# S181A.net
KiCad netlist of a schematic drawn in EAGLE
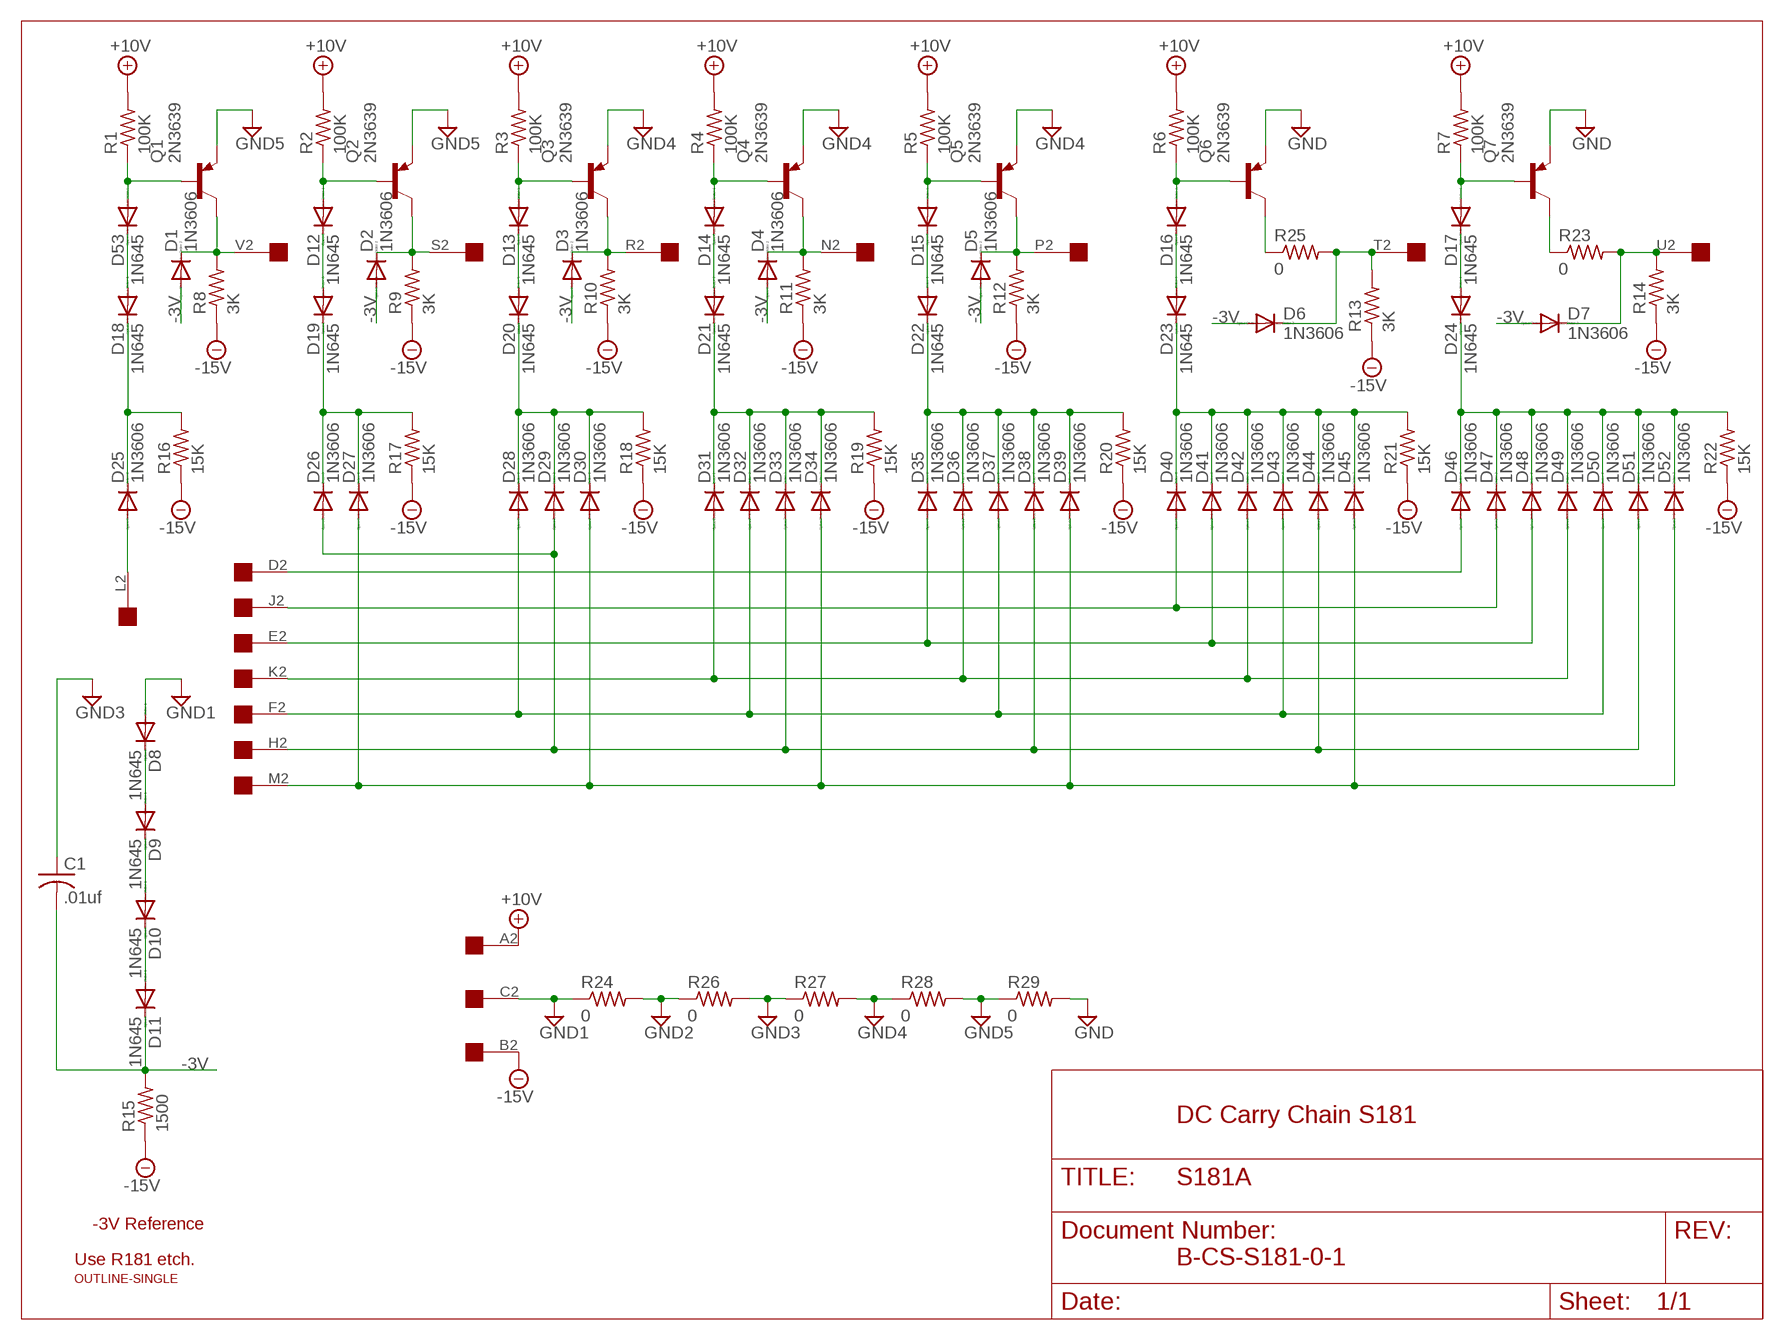
[diagram p0: schematic, sheet 1]

(export (version "E")
  (design (tool "Eeschema 10.0.6"))
  (components
    (comp (ref "C1")
      (value ".01uf")
      (footprint "eagle-import:C050-025X075")
      (libsource (lib "eagle-import") (part "C-US050-025X075"))
    )
    (comp (ref "D1")
      (value "1N3606")
      (footprint "eagle-import:DO35-10")
      (libsource (lib "eagle-import") (part "1N4148DO35-10"))
    )
    (comp (ref "D2")
      (value "1N3606")
      (footprint "eagle-import:DO35-10")
      (libsource (lib "eagle-import") (part "1N4148DO35-10"))
    )
    (comp (ref "D3")
      (value "1N3606")
      (footprint "eagle-import:DO35-10")
      (libsource (lib "eagle-import") (part "1N4148DO35-10"))
    )
    (comp (ref "D4")
      (value "1N3606")
      (footprint "eagle-import:DO35-10")
      (libsource (lib "eagle-import") (part "1N4148DO35-10"))
    )
    (comp (ref "D5")
      (value "1N3606")
      (footprint "eagle-import:DO35-10")
      (libsource (lib "eagle-import") (part "1N4148DO35-10"))
    )
    (comp (ref "D6")
      (value "1N3606")
      (footprint "eagle-import:DO35-10")
      (libsource (lib "eagle-import") (part "1N4148DO35-10"))
    )
    (comp (ref "D7")
      (value "1N3606")
      (footprint "eagle-import:DO35-10")
      (libsource (lib "eagle-import") (part "1N4148DO35-10"))
    )
    (comp (ref "D8")
      (value "1N645")
      (footprint "eagle-import:DO35-10")
      (libsource (lib "eagle-import") (part "1N4148DO35-10"))
    )
    (comp (ref "D9")
      (value "1N645")
      (footprint "eagle-import:DO35-10")
      (libsource (lib "eagle-import") (part "1N4148DO35-10"))
    )
    (comp (ref "D10")
      (value "1N645")
      (footprint "eagle-import:DO35-10")
      (libsource (lib "eagle-import") (part "1N4148DO35-10"))
    )
    (comp (ref "D11")
      (value "1N645")
      (footprint "eagle-import:DO35-10")
      (libsource (lib "eagle-import") (part "1N4148DO35-10"))
    )
    (comp (ref "D12")
      (value "1N645")
      (footprint "eagle-import:DO35-10")
      (libsource (lib "eagle-import") (part "1N4148DO35-10"))
    )
    (comp (ref "D13")
      (value "1N645")
      (footprint "eagle-import:DO35-10")
      (libsource (lib "eagle-import") (part "1N4148DO35-10"))
    )
    (comp (ref "D14")
      (value "1N645")
      (footprint "eagle-import:DO35-10")
      (libsource (lib "eagle-import") (part "1N4148DO35-10"))
    )
    (comp (ref "D15")
      (value "1N645")
      (footprint "eagle-import:DO35-10")
      (libsource (lib "eagle-import") (part "1N4148DO35-10"))
    )
    (comp (ref "D16")
      (value "1N645")
      (footprint "eagle-import:DO35-10")
      (libsource (lib "eagle-import") (part "1N4148DO35-10"))
    )
    (comp (ref "D17")
      (value "1N645")
      (footprint "eagle-import:DO35-10")
      (libsource (lib "eagle-import") (part "1N4148DO35-10"))
    )
    (comp (ref "D18")
      (value "1N645")
      (footprint "eagle-import:DO35-10")
      (libsource (lib "eagle-import") (part "1N4148DO35-10"))
    )
    (comp (ref "D19")
      (value "1N645")
      (footprint "eagle-import:DO35-10")
      (libsource (lib "eagle-import") (part "1N4148DO35-10"))
    )
    (comp (ref "D20")
      (value "1N645")
      (footprint "eagle-import:DO35-10")
      (libsource (lib "eagle-import") (part "1N4148DO35-10"))
    )
    (comp (ref "D21")
      (value "1N645")
      (footprint "eagle-import:DO35-10")
      (libsource (lib "eagle-import") (part "1N4148DO35-10"))
    )
    (comp (ref "D22")
      (value "1N645")
      (footprint "eagle-import:DO35-10")
      (libsource (lib "eagle-import") (part "1N4148DO35-10"))
    )
    (comp (ref "D23")
      (value "1N645")
      (footprint "eagle-import:DO35-10")
      (libsource (lib "eagle-import") (part "1N4148DO35-10"))
    )
    (comp (ref "D24")
      (value "1N645")
      (footprint "eagle-import:DO35-10")
      (libsource (lib "eagle-import") (part "1N4148DO35-10"))
    )
    (comp (ref "D25")
      (value "1N3606")
      (footprint "eagle-import:DO35-10")
      (libsource (lib "eagle-import") (part "1N4148DO35-10"))
    )
    (comp (ref "D26")
      (value "1N3606")
      (footprint "eagle-import:DO35-10")
      (libsource (lib "eagle-import") (part "1N4148DO35-10"))
    )
    (comp (ref "D27")
      (value "1N3606")
      (footprint "eagle-import:DO35-10")
      (libsource (lib "eagle-import") (part "1N4148DO35-10"))
    )
    (comp (ref "D28")
      (value "1N3606")
      (footprint "eagle-import:DO35-10")
      (libsource (lib "eagle-import") (part "1N4148DO35-10"))
    )
    (comp (ref "D29")
      (value "1N3606")
      (footprint "eagle-import:DO35-10")
      (libsource (lib "eagle-import") (part "1N4148DO35-10"))
    )
    (comp (ref "D30")
      (value "1N3606")
      (footprint "eagle-import:DO35-10")
      (libsource (lib "eagle-import") (part "1N4148DO35-10"))
    )
    (comp (ref "D31")
      (value "1N3606")
      (footprint "eagle-import:DO35-10")
      (libsource (lib "eagle-import") (part "1N4148DO35-10"))
    )
    (comp (ref "D32")
      (value "1N3606")
      (footprint "eagle-import:DO35-10")
      (libsource (lib "eagle-import") (part "1N4148DO35-10"))
    )
    (comp (ref "D33")
      (value "1N3606")
      (footprint "eagle-import:DO35-10")
      (libsource (lib "eagle-import") (part "1N4148DO35-10"))
    )
    (comp (ref "D34")
      (value "1N3606")
      (footprint "eagle-import:DO35-10")
      (libsource (lib "eagle-import") (part "1N4148DO35-10"))
    )
    (comp (ref "D35")
      (value "1N3606")
      (footprint "eagle-import:DO35-10")
      (libsource (lib "eagle-import") (part "1N4148DO35-10"))
    )
    (comp (ref "D36")
      (value "1N3606")
      (footprint "eagle-import:DO35-10")
      (libsource (lib "eagle-import") (part "1N4148DO35-10"))
    )
    (comp (ref "D37")
      (value "1N3606")
      (footprint "eagle-import:DO35-10")
      (libsource (lib "eagle-import") (part "1N4148DO35-10"))
    )
    (comp (ref "D38")
      (value "1N3606")
      (footprint "eagle-import:DO35-10")
      (libsource (lib "eagle-import") (part "1N4148DO35-10"))
    )
    (comp (ref "D39")
      (value "1N3606")
      (footprint "eagle-import:DO35-10")
      (libsource (lib "eagle-import") (part "1N4148DO35-10"))
    )
    (comp (ref "D40")
      (value "1N3606")
      (footprint "eagle-import:DO35-10")
      (libsource (lib "eagle-import") (part "1N4148DO35-10"))
    )
    (comp (ref "D41")
      (value "1N3606")
      (footprint "eagle-import:DO35-10")
      (libsource (lib "eagle-import") (part "1N4148DO35-10"))
    )
    (comp (ref "D42")
      (value "1N3606")
      (footprint "eagle-import:DO35-10")
      (libsource (lib "eagle-import") (part "1N4148DO35-10"))
    )
    (comp (ref "D43")
      (value "1N3606")
      (footprint "eagle-import:DO35-10")
      (libsource (lib "eagle-import") (part "1N4148DO35-10"))
    )
    (comp (ref "D44")
      (value "1N3606")
      (footprint "eagle-import:DO35-10")
      (libsource (lib "eagle-import") (part "1N4148DO35-10"))
    )
    (comp (ref "D45")
      (value "1N3606")
      (footprint "eagle-import:DO35-10")
      (libsource (lib "eagle-import") (part "1N4148DO35-10"))
    )
    (comp (ref "D46")
      (value "1N3606")
      (footprint "eagle-import:DO35-10")
      (libsource (lib "eagle-import") (part "1N4148DO35-10"))
    )
    (comp (ref "D47")
      (value "1N3606")
      (footprint "eagle-import:DO35-10")
      (libsource (lib "eagle-import") (part "1N4148DO35-10"))
    )
    (comp (ref "D48")
      (value "1N3606")
      (footprint "eagle-import:DO35-10")
      (libsource (lib "eagle-import") (part "1N4148DO35-10"))
    )
    (comp (ref "D49")
      (value "1N3606")
      (footprint "eagle-import:DO35-10")
      (libsource (lib "eagle-import") (part "1N4148DO35-10"))
    )
    (comp (ref "D50")
      (value "1N3606")
      (footprint "eagle-import:DO35-10")
      (libsource (lib "eagle-import") (part "1N4148DO35-10"))
    )
    (comp (ref "D51")
      (value "1N3606")
      (footprint "eagle-import:DO35-10")
      (libsource (lib "eagle-import") (part "1N4148DO35-10"))
    )
    (comp (ref "D52")
      (value "1N3606")
      (footprint "eagle-import:DO35-10")
      (libsource (lib "eagle-import") (part "1N4148DO35-10"))
    )
    (comp (ref "D53")
      (value "1N645")
      (footprint "eagle-import:DO35-10")
      (libsource (lib "eagle-import") (part "1N4148DO35-10"))
    )
    (comp (ref "Q1")
      (value "2N3639")
      (footprint "eagle-import:TO39")
      (libsource (lib "eagle-import") (part "2N3637"))
    )
    (comp (ref "Q2")
      (value "2N3639")
      (footprint "eagle-import:TO39")
      (libsource (lib "eagle-import") (part "2N3637"))
    )
    (comp (ref "Q3")
      (value "2N3639")
      (footprint "eagle-import:TO39")
      (libsource (lib "eagle-import") (part "2N3637"))
    )
    (comp (ref "Q4")
      (value "2N3639")
      (footprint "eagle-import:TO39")
      (libsource (lib "eagle-import") (part "2N3637"))
    )
    (comp (ref "Q5")
      (value "2N3639")
      (footprint "eagle-import:TO39")
      (libsource (lib "eagle-import") (part "2N3637"))
    )
    (comp (ref "Q6")
      (value "2N3639")
      (footprint "eagle-import:TO39")
      (libsource (lib "eagle-import") (part "2N3637"))
    )
    (comp (ref "Q7")
      (value "2N3639")
      (footprint "eagle-import:TO39")
      (libsource (lib "eagle-import") (part "2N3637"))
    )
    (comp (ref "R1")
      (value "100K")
      (footprint "eagle-import:0207_10")
      (libsource (lib "eagle-import") (part "R-US_0207/10"))
    )
    (comp (ref "R2")
      (value "100K")
      (footprint "eagle-import:0207_10")
      (libsource (lib "eagle-import") (part "R-US_0207/10"))
    )
    (comp (ref "R3")
      (value "100K")
      (footprint "eagle-import:0207_10")
      (libsource (lib "eagle-import") (part "R-US_0207/10"))
    )
    (comp (ref "R4")
      (value "100K")
      (footprint "eagle-import:0207_10")
      (libsource (lib "eagle-import") (part "R-US_0207/10"))
    )
    (comp (ref "R5")
      (value "100K")
      (footprint "eagle-import:0207_10")
      (libsource (lib "eagle-import") (part "R-US_0207/10"))
    )
    (comp (ref "R6")
      (value "100K")
      (footprint "eagle-import:0207_10")
      (libsource (lib "eagle-import") (part "R-US_0207/10"))
    )
    (comp (ref "R7")
      (value "100K")
      (footprint "eagle-import:0207_10")
      (libsource (lib "eagle-import") (part "R-US_0207/10"))
    )
    (comp (ref "R8")
      (value "3K")
      (footprint "eagle-import:0207_10")
      (libsource (lib "eagle-import") (part "R-US_0207/10"))
    )
    (comp (ref "R9")
      (value "3K")
      (footprint "eagle-import:0207_10")
      (libsource (lib "eagle-import") (part "R-US_0207/10"))
    )
    (comp (ref "R10")
      (value "3K")
      (footprint "eagle-import:0207_10")
      (libsource (lib "eagle-import") (part "R-US_0207/10"))
    )
    (comp (ref "R11")
      (value "3K")
      (footprint "eagle-import:0207_10")
      (libsource (lib "eagle-import") (part "R-US_0207/10"))
    )
    (comp (ref "R12")
      (value "3K")
      (footprint "eagle-import:0207_10")
      (libsource (lib "eagle-import") (part "R-US_0207/10"))
    )
    (comp (ref "R13")
      (value "3K")
      (footprint "eagle-import:0207_10")
      (libsource (lib "eagle-import") (part "R-US_0207/10"))
    )
    (comp (ref "R14")
      (value "3K")
      (footprint "eagle-import:0207_10")
      (libsource (lib "eagle-import") (part "R-US_0207/10"))
    )
    (comp (ref "R15")
      (value "1500")
      (footprint "eagle-import:0207_10")
      (libsource (lib "eagle-import") (part "R-US_0207/10"))
    )
    (comp (ref "R16")
      (value "15K")
      (footprint "eagle-import:0207_10")
      (libsource (lib "eagle-import") (part "R-US_0207/10"))
    )
    (comp (ref "R17")
      (value "15K")
      (footprint "eagle-import:0207_10")
      (libsource (lib "eagle-import") (part "R-US_0207/10"))
    )
    (comp (ref "R18")
      (value "15K")
      (footprint "eagle-import:0207_10")
      (libsource (lib "eagle-import") (part "R-US_0207/10"))
    )
    (comp (ref "R19")
      (value "15K")
      (footprint "eagle-import:0207_10")
      (libsource (lib "eagle-import") (part "R-US_0207/10"))
    )
    (comp (ref "R20")
      (value "15K")
      (footprint "eagle-import:0207_10")
      (libsource (lib "eagle-import") (part "R-US_0207/10"))
    )
    (comp (ref "R21")
      (value "15K")
      (footprint "eagle-import:0207_10")
      (libsource (lib "eagle-import") (part "R-US_0207/10"))
    )
    (comp (ref "R22")
      (value "15K")
      (footprint "eagle-import:0207_10")
      (libsource (lib "eagle-import") (part "R-US_0207/10"))
    )
    (comp (ref "R23")
      (value "0")
      (footprint "eagle-import:0207_10")
      (libsource (lib "eagle-import") (part "R-US_0207/10"))
    )
    (comp (ref "R24")
      (value "0")
      (footprint "eagle-import:0207_10")
      (libsource (lib "eagle-import") (part "R-US_0207/10"))
    )
    (comp (ref "R25")
      (value "0")
      (footprint "eagle-import:0207_10")
      (libsource (lib "eagle-import") (part "R-US_0207/10"))
    )
    (comp (ref "R26")
      (value "0")
      (footprint "eagle-import:0207_10")
      (libsource (lib "eagle-import") (part "R-US_0207/10"))
    )
    (comp (ref "R27")
      (value "0")
      (footprint "eagle-import:0207_10")
      (libsource (lib "eagle-import") (part "R-US_0207/10"))
    )
    (comp (ref "R28")
      (value "0")
      (footprint "eagle-import:0207_10")
      (libsource (lib "eagle-import") (part "R-US_0207/10"))
    )
    (comp (ref "R29")
      (value "0")
      (footprint "eagle-import:0207_10")
      (libsource (lib "eagle-import") (part "R-US_0207/10"))
    )
    (comp (ref "U$1")
      (value "OUTLINE-SINGLE")
      (footprint "eagle-import:SINGLE")
      (libsource (lib "eagle-import") (part "OUTLINE-SINGLE"))
    )
    (comp (ref "U$2")
      (value "EDGE-1")
      (footprint "eagle-import:EDGE-CON1")
      (libsource (lib "eagle-import") (part "EDGE-1"))
    )
  )
  (nets
    (net (code "1") (name "+10V") (class "Default")
      (node (ref "R1") (pin "2") (pinfunction "2_2") (pintype "passive"))
      (node (ref "R2") (pin "2") (pinfunction "2_2") (pintype "passive"))
      (node (ref "R3") (pin "2") (pinfunction "2_2") (pintype "passive"))
      (node (ref "R4") (pin "2") (pinfunction "2_2") (pintype "passive"))
      (node (ref "R5") (pin "2") (pinfunction "2_2") (pintype "passive"))
      (node (ref "R6") (pin "2") (pinfunction "2_2") (pintype "passive"))
      (node (ref "R7") (pin "2") (pinfunction "2_2") (pintype "passive"))
      (node (ref "U$2") (pin "A2") (pinfunction "1_A2") (pintype "bidirectional"))
    )
    (net (code "2") (name "-15V") (class "Default")
      (node (ref "R10") (pin "1") (pinfunction "1_1") (pintype "passive"))
      (node (ref "R11") (pin "1") (pinfunction "1_1") (pintype "passive"))
      (node (ref "R12") (pin "1") (pinfunction "1_1") (pintype "passive"))
      (node (ref "R13") (pin "1") (pinfunction "1_1") (pintype "passive"))
      (node (ref "R14") (pin "1") (pinfunction "1_1") (pintype "passive"))
      (node (ref "R15") (pin "1") (pinfunction "1_1") (pintype "passive"))
      (node (ref "R16") (pin "1") (pinfunction "1_1") (pintype "passive"))
      (node (ref "R17") (pin "1") (pinfunction "1_1") (pintype "passive"))
      (node (ref "R18") (pin "1") (pinfunction "1_1") (pintype "passive"))
      (node (ref "R19") (pin "1") (pinfunction "1_1") (pintype "passive"))
      (node (ref "R20") (pin "1") (pinfunction "1_1") (pintype "passive"))
      (node (ref "R21") (pin "1") (pinfunction "1_1") (pintype "passive"))
      (node (ref "R22") (pin "1") (pinfunction "1_1") (pintype "passive"))
      (node (ref "R8") (pin "1") (pinfunction "1_1") (pintype "passive"))
      (node (ref "R9") (pin "1") (pinfunction "1_1") (pintype "passive"))
      (node (ref "U$2") (pin "B2") (pinfunction "1_B2") (pintype "bidirectional"))
    )
    (net (code "3") (name "/-3V") (class "Default")
      (node (ref "C1") (pin "2") (pinfunction "2_2") (pintype "passive"))
      (node (ref "D1") (pin "A") (pinfunction "A_A") (pintype "passive"))
      (node (ref "D11") (pin "C") (pinfunction "C_C") (pintype "passive"))
      (node (ref "D2") (pin "A") (pinfunction "A_A") (pintype "passive"))
      (node (ref "D3") (pin "A") (pinfunction "A_A") (pintype "passive"))
      (node (ref "D4") (pin "A") (pinfunction "A_A") (pintype "passive"))
      (node (ref "D5") (pin "A") (pinfunction "A_A") (pintype "passive"))
      (node (ref "D6") (pin "A") (pinfunction "A_A") (pintype "passive"))
      (node (ref "D7") (pin "A") (pinfunction "A_A") (pintype "passive"))
      (node (ref "R15") (pin "2") (pinfunction "2_2") (pintype "passive"))
    )
    (net (code "4") (name "GND") (class "Default")
      (node (ref "Q6") (pin "1") (pinfunction "E_1") (pintype "passive"))
      (node (ref "Q7") (pin "1") (pinfunction "E_1") (pintype "passive"))
      (node (ref "R29") (pin "2") (pinfunction "2_2") (pintype "passive"))
    )
    (net (code "5") (name "GND1") (class "Default")
      (node (ref "D8") (pin "A") (pinfunction "A_A") (pintype "passive"))
      (node (ref "R24") (pin "1") (pinfunction "1_1") (pintype "passive"))
      (node (ref "U$2") (pin "C2") (pinfunction "1_C2") (pintype "bidirectional"))
    )
    (net (code "6") (name "GND2") (class "Default")
      (node (ref "R24") (pin "2") (pinfunction "2_2") (pintype "passive"))
      (node (ref "R26") (pin "1") (pinfunction "1_1") (pintype "passive"))
    )
    (net (code "7") (name "GND3") (class "Default")
      (node (ref "C1") (pin "1") (pinfunction "1_1") (pintype "passive"))
      (node (ref "R26") (pin "2") (pinfunction "2_2") (pintype "passive"))
      (node (ref "R27") (pin "1") (pinfunction "1_1") (pintype "passive"))
    )
    (net (code "8") (name "GND4") (class "Default")
      (node (ref "Q3") (pin "1") (pinfunction "E_1") (pintype "passive"))
      (node (ref "Q4") (pin "1") (pinfunction "E_1") (pintype "passive"))
      (node (ref "Q5") (pin "1") (pinfunction "E_1") (pintype "passive"))
      (node (ref "R27") (pin "2") (pinfunction "2_2") (pintype "passive"))
      (node (ref "R28") (pin "1") (pinfunction "1_1") (pintype "passive"))
    )
    (net (code "9") (name "GND5") (class "Default")
      (node (ref "Q1") (pin "1") (pinfunction "E_1") (pintype "passive"))
      (node (ref "Q2") (pin "1") (pinfunction "E_1") (pintype "passive"))
      (node (ref "R28") (pin "2") (pinfunction "2_2") (pintype "passive"))
      (node (ref "R29") (pin "1") (pinfunction "1_1") (pintype "passive"))
    )
    (net (code "10") (name "Net-(D8-PadC)") (class "Default")
      (node (ref "D8") (pin "C") (pinfunction "C_C") (pintype "passive"))
      (node (ref "D9") (pin "A") (pinfunction "A_A") (pintype "passive"))
    )
    (net (code "11") (name "Net-(D10-PadA)") (class "Default")
      (node (ref "D10") (pin "A") (pinfunction "A_A") (pintype "passive"))
      (node (ref "D9") (pin "C") (pinfunction "C_C") (pintype "passive"))
    )
    (net (code "12") (name "Net-(D10-PadC)") (class "Default")
      (node (ref "D10") (pin "C") (pinfunction "C_C") (pintype "passive"))
      (node (ref "D11") (pin "A") (pinfunction "A_A") (pintype "passive"))
    )
    (net (code "13") (name "Net-(D12-PadC)") (class "Default")
      (node (ref "D12") (pin "C") (pinfunction "C_C") (pintype "passive"))
      (node (ref "D19") (pin "A") (pinfunction "A_A") (pintype "passive"))
    )
    (net (code "14") (name "Net-(D13-PadC)") (class "Default")
      (node (ref "D13") (pin "C") (pinfunction "C_C") (pintype "passive"))
      (node (ref "D20") (pin "A") (pinfunction "A_A") (pintype "passive"))
    )
    (net (code "15") (name "Net-(D14-PadC)") (class "Default")
      (node (ref "D14") (pin "C") (pinfunction "C_C") (pintype "passive"))
      (node (ref "D21") (pin "A") (pinfunction "A_A") (pintype "passive"))
    )
    (net (code "16") (name "Net-(D15-PadC)") (class "Default")
      (node (ref "D15") (pin "C") (pinfunction "C_C") (pintype "passive"))
      (node (ref "D22") (pin "A") (pinfunction "A_A") (pintype "passive"))
    )
    (net (code "17") (name "Net-(D16-PadC)") (class "Default")
      (node (ref "D16") (pin "C") (pinfunction "C_C") (pintype "passive"))
      (node (ref "D23") (pin "A") (pinfunction "A_A") (pintype "passive"))
    )
    (net (code "18") (name "Net-(D17-PadC)") (class "Default")
      (node (ref "D17") (pin "C") (pinfunction "C_C") (pintype "passive"))
      (node (ref "D24") (pin "A") (pinfunction "A_A") (pintype "passive"))
    )
    (net (code "19") (name "Net-(D18-PadA)") (class "Default")
      (node (ref "D18") (pin "A") (pinfunction "A_A") (pintype "passive"))
      (node (ref "D53") (pin "C") (pinfunction "C_C") (pintype "passive"))
    )
    (net (code "20") (name "Net-(D18-PadC)") (class "Default")
      (node (ref "D18") (pin "C") (pinfunction "C_C") (pintype "passive"))
      (node (ref "D25") (pin "C") (pinfunction "C_C") (pintype "passive"))
      (node (ref "R16") (pin "2") (pinfunction "2_2") (pintype "passive"))
    )
    (net (code "21") (name "Net-(D19-PadC)") (class "Default")
      (node (ref "D19") (pin "C") (pinfunction "C_C") (pintype "passive"))
      (node (ref "D26") (pin "C") (pinfunction "C_C") (pintype "passive"))
      (node (ref "D27") (pin "C") (pinfunction "C_C") (pintype "passive"))
      (node (ref "R17") (pin "2") (pinfunction "2_2") (pintype "passive"))
    )
    (net (code "22") (name "Net-(D20-PadC)") (class "Default")
      (node (ref "D20") (pin "C") (pinfunction "C_C") (pintype "passive"))
      (node (ref "D28") (pin "C") (pinfunction "C_C") (pintype "passive"))
      (node (ref "D29") (pin "C") (pinfunction "C_C") (pintype "passive"))
      (node (ref "D30") (pin "C") (pinfunction "C_C") (pintype "passive"))
      (node (ref "R18") (pin "2") (pinfunction "2_2") (pintype "passive"))
    )
    (net (code "23") (name "Net-(D21-PadC)") (class "Default")
      (node (ref "D21") (pin "C") (pinfunction "C_C") (pintype "passive"))
      (node (ref "D31") (pin "C") (pinfunction "C_C") (pintype "passive"))
      (node (ref "D32") (pin "C") (pinfunction "C_C") (pintype "passive"))
      (node (ref "D33") (pin "C") (pinfunction "C_C") (pintype "passive"))
      (node (ref "D34") (pin "C") (pinfunction "C_C") (pintype "passive"))
      (node (ref "R19") (pin "2") (pinfunction "2_2") (pintype "passive"))
    )
    (net (code "24") (name "Net-(D22-PadC)") (class "Default")
      (node (ref "D22") (pin "C") (pinfunction "C_C") (pintype "passive"))
      (node (ref "D35") (pin "C") (pinfunction "C_C") (pintype "passive"))
      (node (ref "D36") (pin "C") (pinfunction "C_C") (pintype "passive"))
      (node (ref "D37") (pin "C") (pinfunction "C_C") (pintype "passive"))
      (node (ref "D38") (pin "C") (pinfunction "C_C") (pintype "passive"))
      (node (ref "D39") (pin "C") (pinfunction "C_C") (pintype "passive"))
      (node (ref "R20") (pin "2") (pinfunction "2_2") (pintype "passive"))
    )
    (net (code "25") (name "Net-(D23-PadC)") (class "Default")
      (node (ref "D23") (pin "C") (pinfunction "C_C") (pintype "passive"))
      (node (ref "D40") (pin "C") (pinfunction "C_C") (pintype "passive"))
      (node (ref "D41") (pin "C") (pinfunction "C_C") (pintype "passive"))
      (node (ref "D42") (pin "C") (pinfunction "C_C") (pintype "passive"))
      (node (ref "D43") (pin "C") (pinfunction "C_C") (pintype "passive"))
      (node (ref "D44") (pin "C") (pinfunction "C_C") (pintype "passive"))
      (node (ref "D45") (pin "C") (pinfunction "C_C") (pintype "passive"))
      (node (ref "R21") (pin "2") (pinfunction "2_2") (pintype "passive"))
    )
    (net (code "26") (name "Net-(D24-PadC)") (class "Default")
      (node (ref "D24") (pin "C") (pinfunction "C_C") (pintype "passive"))
      (node (ref "D46") (pin "C") (pinfunction "C_C") (pintype "passive"))
      (node (ref "D47") (pin "C") (pinfunction "C_C") (pintype "passive"))
      (node (ref "D48") (pin "C") (pinfunction "C_C") (pintype "passive"))
      (node (ref "D49") (pin "C") (pinfunction "C_C") (pintype "passive"))
      (node (ref "D50") (pin "C") (pinfunction "C_C") (pintype "passive"))
      (node (ref "D51") (pin "C") (pinfunction "C_C") (pintype "passive"))
      (node (ref "D52") (pin "C") (pinfunction "C_C") (pintype "passive"))
      (node (ref "R22") (pin "2") (pinfunction "2_2") (pintype "passive"))
    )
    (net (code "27") (name "Net-(Q1-B)") (class "Default")
      (node (ref "D53") (pin "A") (pinfunction "A_A") (pintype "passive"))
      (node (ref "Q1") (pin "2") (pinfunction "B_2") (pintype "passive"))
      (node (ref "R1") (pin "1") (pinfunction "1_1") (pintype "passive"))
    )
    (net (code "28") (name "Net-(Q1-C)") (class "Default")
      (node (ref "D1") (pin "C") (pinfunction "C_C") (pintype "passive"))
      (node (ref "Q1") (pin "3") (pinfunction "C_3") (pintype "passive"))
      (node (ref "R8") (pin "2") (pinfunction "2_2") (pintype "passive"))
      (node (ref "U$2") (pin "V2") (pinfunction "1_V2") (pintype "bidirectional"))
    )
    (net (code "29") (name "Net-(Q2-B)") (class "Default")
      (node (ref "D12") (pin "A") (pinfunction "A_A") (pintype "passive"))
      (node (ref "Q2") (pin "2") (pinfunction "B_2") (pintype "passive"))
      (node (ref "R2") (pin "1") (pinfunction "1_1") (pintype "passive"))
    )
    (net (code "30") (name "Net-(Q2-C)") (class "Default")
      (node (ref "D2") (pin "C") (pinfunction "C_C") (pintype "passive"))
      (node (ref "Q2") (pin "3") (pinfunction "C_3") (pintype "passive"))
      (node (ref "R9") (pin "2") (pinfunction "2_2") (pintype "passive"))
      (node (ref "U$2") (pin "S2") (pinfunction "1_S2") (pintype "bidirectional"))
    )
    (net (code "31") (name "Net-(Q3-B)") (class "Default")
      (node (ref "D13") (pin "A") (pinfunction "A_A") (pintype "passive"))
      (node (ref "Q3") (pin "2") (pinfunction "B_2") (pintype "passive"))
      (node (ref "R3") (pin "1") (pinfunction "1_1") (pintype "passive"))
    )
    (net (code "32") (name "Net-(Q3-C)") (class "Default")
      (node (ref "D3") (pin "C") (pinfunction "C_C") (pintype "passive"))
      (node (ref "Q3") (pin "3") (pinfunction "C_3") (pintype "passive"))
      (node (ref "R10") (pin "2") (pinfunction "2_2") (pintype "passive"))
      (node (ref "U$2") (pin "R2") (pinfunction "1_R2") (pintype "bidirectional"))
    )
    (net (code "33") (name "Net-(Q4-B)") (class "Default")
      (node (ref "D14") (pin "A") (pinfunction "A_A") (pintype "passive"))
      (node (ref "Q4") (pin "2") (pinfunction "B_2") (pintype "passive"))
      (node (ref "R4") (pin "1") (pinfunction "1_1") (pintype "passive"))
    )
    (net (code "34") (name "Net-(Q4-C)") (class "Default")
      (node (ref "D4") (pin "C") (pinfunction "C_C") (pintype "passive"))
      (node (ref "Q4") (pin "3") (pinfunction "C_3") (pintype "passive"))
      (node (ref "R11") (pin "2") (pinfunction "2_2") (pintype "passive"))
      (node (ref "U$2") (pin "N2") (pinfunction "1_N2") (pintype "bidirectional"))
    )
    (net (code "35") (name "Net-(Q5-B)") (class "Default")
      (node (ref "D15") (pin "A") (pinfunction "A_A") (pintype "passive"))
      (node (ref "Q5") (pin "2") (pinfunction "B_2") (pintype "passive"))
      (node (ref "R5") (pin "1") (pinfunction "1_1") (pintype "passive"))
    )
    (net (code "36") (name "Net-(Q5-C)") (class "Default")
      (node (ref "D5") (pin "C") (pinfunction "C_C") (pintype "passive"))
      (node (ref "Q5") (pin "3") (pinfunction "C_3") (pintype "passive"))
      (node (ref "R12") (pin "2") (pinfunction "2_2") (pintype "passive"))
      (node (ref "U$2") (pin "P2") (pinfunction "1_P2") (pintype "bidirectional"))
    )
    (net (code "37") (name "Net-(Q6-B)") (class "Default")
      (node (ref "D16") (pin "A") (pinfunction "A_A") (pintype "passive"))
      (node (ref "Q6") (pin "2") (pinfunction "B_2") (pintype "passive"))
      (node (ref "R6") (pin "1") (pinfunction "1_1") (pintype "passive"))
    )
    (net (code "38") (name "Net-(Q6-C)") (class "Default")
      (node (ref "Q6") (pin "3") (pinfunction "C_3") (pintype "passive"))
      (node (ref "R25") (pin "1") (pinfunction "1_1") (pintype "passive"))
    )
    (net (code "39") (name "Net-(Q7-B)") (class "Default")
      (node (ref "D17") (pin "A") (pinfunction "A_A") (pintype "passive"))
      (node (ref "Q7") (pin "2") (pinfunction "B_2") (pintype "passive"))
      (node (ref "R7") (pin "1") (pinfunction "1_1") (pintype "passive"))
    )
    (net (code "40") (name "Net-(Q7-C)") (class "Default")
      (node (ref "Q7") (pin "3") (pinfunction "C_3") (pintype "passive"))
      (node (ref "R23") (pin "1") (pinfunction "1_1") (pintype "passive"))
    )
    (net (code "41") (name "Net-(U$2D-1)") (class "Default")
      (node (ref "D46") (pin "A") (pinfunction "A_A") (pintype "passive"))
      (node (ref "U$2") (pin "D2") (pinfunction "1_D2") (pintype "bidirectional"))
    )
    (net (code "42") (name "Net-(U$2E-1)") (class "Default")
      (node (ref "D35") (pin "A") (pinfunction "A_A") (pintype "passive"))
      (node (ref "D41") (pin "A") (pinfunction "A_A") (pintype "passive"))
      (node (ref "D48") (pin "A") (pinfunction "A_A") (pintype "passive"))
      (node (ref "U$2") (pin "E2") (pinfunction "1_E2") (pintype "bidirectional"))
    )
    (net (code "43") (name "Net-(U$2F-1)") (class "Default")
      (node (ref "D28") (pin "A") (pinfunction "A_A") (pintype "passive"))
      (node (ref "D32") (pin "A") (pinfunction "A_A") (pintype "passive"))
      (node (ref "D37") (pin "A") (pinfunction "A_A") (pintype "passive"))
      (node (ref "D43") (pin "A") (pinfunction "A_A") (pintype "passive"))
      (node (ref "D50") (pin "A") (pinfunction "A_A") (pintype "passive"))
      (node (ref "U$2") (pin "F2") (pinfunction "1_F2") (pintype "bidirectional"))
    )
    (net (code "44") (name "Net-(U$2G-1)") (class "Default")
      (node (ref "D26") (pin "A") (pinfunction "A_A") (pintype "passive"))
      (node (ref "D29") (pin "A") (pinfunction "A_A") (pintype "passive"))
      (node (ref "D33") (pin "A") (pinfunction "A_A") (pintype "passive"))
      (node (ref "D38") (pin "A") (pinfunction "A_A") (pintype "passive"))
      (node (ref "D44") (pin "A") (pinfunction "A_A") (pintype "passive"))
      (node (ref "D51") (pin "A") (pinfunction "A_A") (pintype "passive"))
      (node (ref "U$2") (pin "H2") (pinfunction "1_H2") (pintype "bidirectional"))
    )
    (net (code "45") (name "Net-(U$2H-1)") (class "Default")
      (node (ref "D40") (pin "A") (pinfunction "A_A") (pintype "passive"))
      (node (ref "D47") (pin "A") (pinfunction "A_A") (pintype "passive"))
      (node (ref "U$2") (pin "J2") (pinfunction "1_J2") (pintype "bidirectional"))
    )
    (net (code "46") (name "Net-(U$2I-1)") (class "Default")
      (node (ref "D31") (pin "A") (pinfunction "A_A") (pintype "passive"))
      (node (ref "D36") (pin "A") (pinfunction "A_A") (pintype "passive"))
      (node (ref "D42") (pin "A") (pinfunction "A_A") (pintype "passive"))
      (node (ref "D49") (pin "A") (pinfunction "A_A") (pintype "passive"))
      (node (ref "U$2") (pin "K2") (pinfunction "1_K2") (pintype "bidirectional"))
    )
    (net (code "47") (name "Net-(U$2J-1)") (class "Default")
      (node (ref "D25") (pin "A") (pinfunction "A_A") (pintype "passive"))
      (node (ref "U$2") (pin "L2") (pinfunction "1_L2") (pintype "bidirectional"))
    )
    (net (code "48") (name "Net-(U$2K-1)") (class "Default")
      (node (ref "D27") (pin "A") (pinfunction "A_A") (pintype "passive"))
      (node (ref "D30") (pin "A") (pinfunction "A_A") (pintype "passive"))
      (node (ref "D34") (pin "A") (pinfunction "A_A") (pintype "passive"))
      (node (ref "D39") (pin "A") (pinfunction "A_A") (pintype "passive"))
      (node (ref "D45") (pin "A") (pinfunction "A_A") (pintype "passive"))
      (node (ref "D52") (pin "A") (pinfunction "A_A") (pintype "passive"))
      (node (ref "U$2") (pin "M2") (pinfunction "1_M2") (pintype "bidirectional"))
    )
    (net (code "49") (name "Net-(U$2P-1)") (class "Default")
      (node (ref "D6") (pin "C") (pinfunction "C_C") (pintype "passive"))
      (node (ref "R13") (pin "2") (pinfunction "2_2") (pintype "passive"))
      (node (ref "R25") (pin "2") (pinfunction "2_2") (pintype "passive"))
      (node (ref "U$2") (pin "T2") (pinfunction "1_T2") (pintype "bidirectional"))
    )
    (net (code "50") (name "Net-(U$2Q-1)") (class "Default")
      (node (ref "D7") (pin "C") (pinfunction "C_C") (pintype "passive"))
      (node (ref "R14") (pin "2") (pinfunction "2_2") (pintype "passive"))
      (node (ref "R23") (pin "2") (pinfunction "2_2") (pintype "passive"))
      (node (ref "U$2") (pin "U2") (pinfunction "1_U2") (pintype "bidirectional"))
    )
  )
)
